# TP_IHM_7SEG.net
KiCad netlist of a schematic drawn in Altium Designer
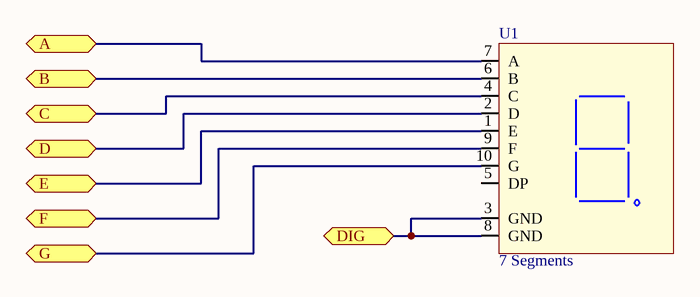
[diagram p0: TP_IHM_7SEG.SchDoc]

(export (version "E")
  (design (tool "Eeschema 10.0.6"))
  (components
    (comp (ref "U1")
      (value "7 Segments")
      (footprint "SA10-21GWA")
      (description "KingBright Led 7 Segments")
      (libsource (lib "TpGiven") (part "SC10-21SRWA"))
    )
  )
  (nets
    (net (code "1") (name "/A") (class "Default")
      (node (ref "U1") (pin "7") (pinfunction "A_7") (pintype "passive"))
    )
    (net (code "2") (name "/B") (class "Default")
      (node (ref "U1") (pin "6") (pinfunction "B_6") (pintype "passive"))
    )
    (net (code "3") (name "/C") (class "Default")
      (node (ref "U1") (pin "4") (pinfunction "C_4") (pintype "passive"))
    )
    (net (code "4") (name "/D") (class "Default")
      (node (ref "U1") (pin "2") (pinfunction "D_2") (pintype "passive"))
    )
    (net (code "5") (name "/DIG") (class "Default")
      (node (ref "U1") (pin "3") (pinfunction "GND_3") (pintype "passive"))
      (node (ref "U1") (pin "8") (pinfunction "GND_8") (pintype "passive"))
    )
    (net (code "6") (name "/E") (class "Default")
      (node (ref "U1") (pin "1") (pinfunction "E_1") (pintype "passive"))
    )
    (net (code "7") (name "/F") (class "Default")
      (node (ref "U1") (pin "9") (pinfunction "F_9") (pintype "passive"))
    )
    (net (code "8") (name "/G") (class "Default")
      (node (ref "U1") (pin "10") (pinfunction "G_10") (pintype "passive"))
    )
    (net (code "9") (name "unconnected-(U1-DP-Pad5)") (class "Default")
      (node (ref "U1") (pin "5") (pinfunction "DP_5") (pintype "passive"))
    )
  )
)
